# CPU_22032016.net
KiCad netlist of a schematic drawn in Altium Designer
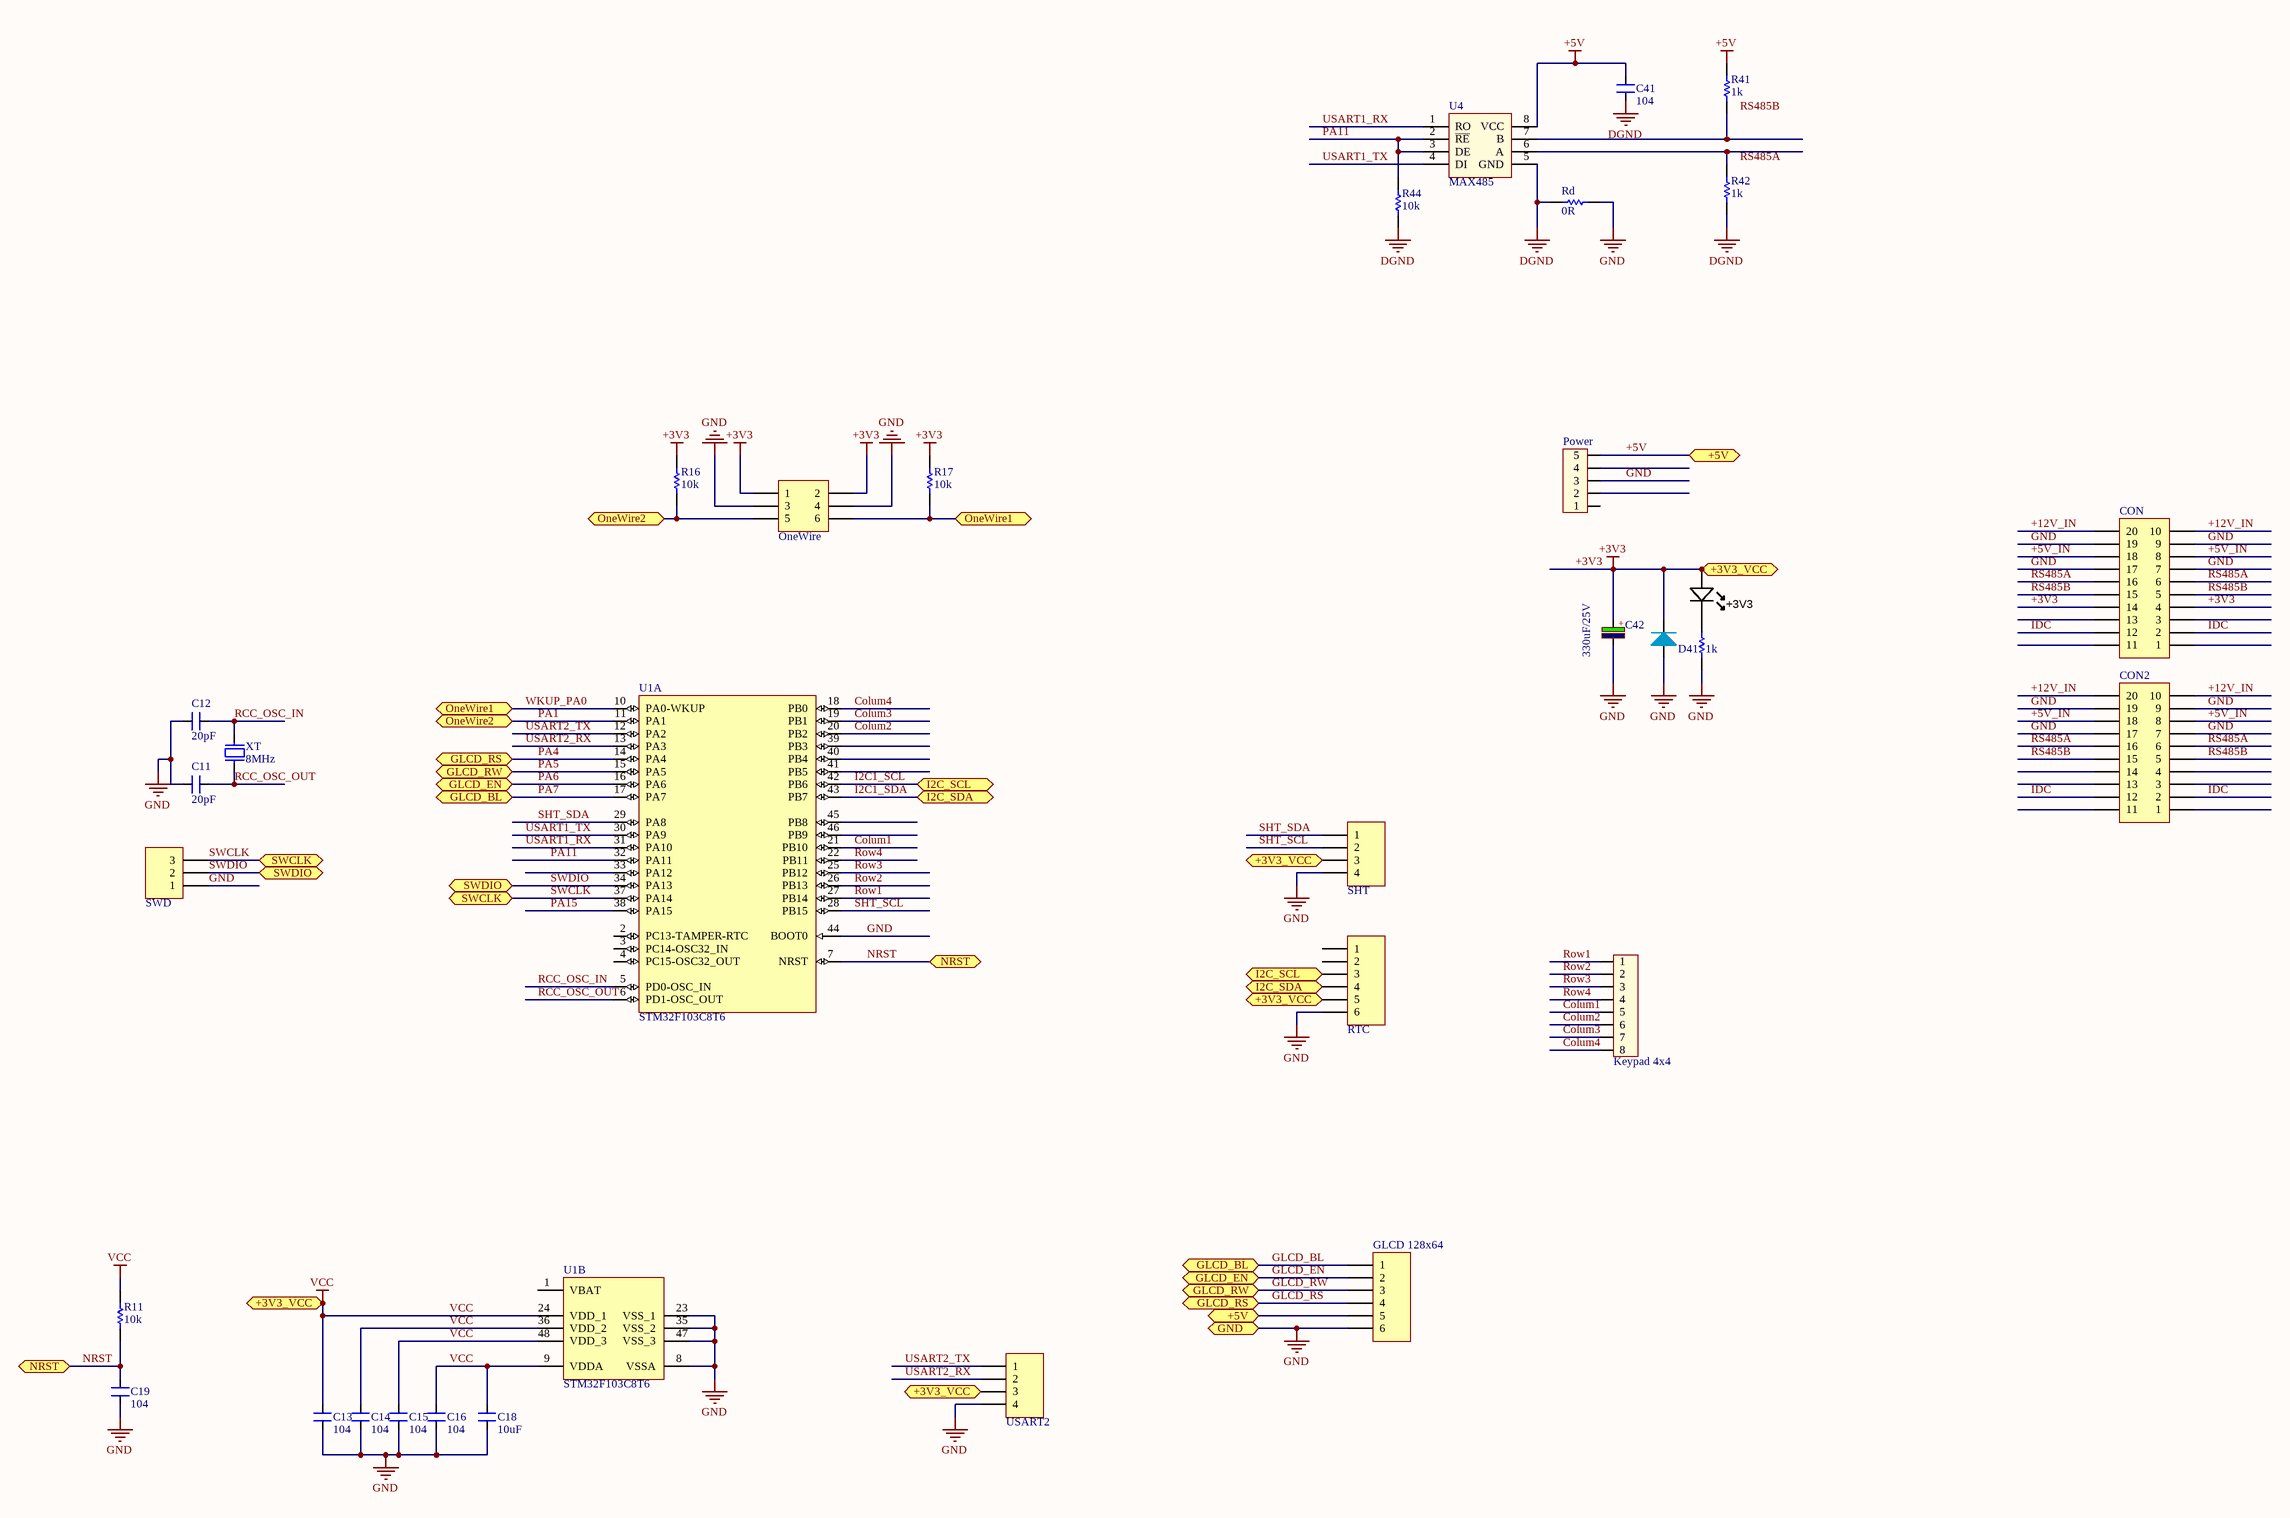
[diagram p0: CPU_22032016.SchDoc]

(export (version "E")
  (design (tool "Eeschema 10.0.6"))
  (components
    (comp (ref "+3V3")
      (value "Blue")
      (footprint "LED-0805-K")
      (description "LED 0805 SMD Blue 100mcd 470nm")
      (libsource (lib "PBL - Light Sources") (part "LED_SMD_Blue_0805_100mcd"))
    )
    (comp (ref "C11")
      (value "20pF")
      (footprint "CAPC1608N")
      (fields (field (name "Comment") "Cap_22p_0603"))
      (libsource (lib "Tuan") (part "CAP NP"))
    )
    (comp (ref "C12")
      (value "20pF")
      (footprint "CAPC1608N")
      (fields (field (name "Comment") "Cap_22p_0603"))
      (libsource (lib "Tuan") (part "CAP NP"))
    )
    (comp (ref "C13")
      (value "104")
      (footprint "CAPC1608N")
      (fields (field (name "Comment") "Cap_104_0603"))
      (libsource (lib "Tuan") (part "CAP NP"))
    )
    (comp (ref "C14")
      (value "104")
      (footprint "CAPC1608N")
      (fields (field (name "Comment") "Cap_104_0603"))
      (libsource (lib "Tuan") (part "CAP NP"))
    )
    (comp (ref "C15")
      (value "104")
      (footprint "CAPC1608N")
      (fields (field (name "Comment") "Cap_104_0603"))
      (libsource (lib "Tuan") (part "CAP NP"))
    )
    (comp (ref "C16")
      (value "104")
      (footprint "CAPC1608N")
      (fields (field (name "Comment") "Cap_104_0603"))
      (libsource (lib "Tuan") (part "CAP NP"))
    )
    (comp (ref "C18")
      (value "10uF")
      (footprint "CAPC2012N_F")
      (fields (field (name "Comment") "Cap_10uF_0805"))
      (libsource (lib "Tuan") (part "CAP NP"))
    )
    (comp (ref "C19")
      (value "104")
      (footprint "CAPC1608N")
      (fields (field (name "Comment") "Cap_104_0603"))
      (libsource (lib "Tuan") (part "CAP NP"))
    )
    (comp (ref "C41")
      (value "104")
      (footprint "CAPC2012N_F")
      (fields (field (name "Comment") "100nF/104"))
      (libsource (lib "Tuan") (part "CAP NP"))
    )
    (comp (ref "C42")
      (value "330uF/25V")
      (footprint "CAPMP3528X210N")
      (description "Cap 1000uF/16V - 220uF/50V")
      (libsource (lib "heromap") (part "CP4"))
    )
    (comp (ref "CON")
      (value "Header 10X2A")
      (footprint "OMC10")
      (description "Header, 10-Pin, Dual row")
      (fields (field (name "PUBLISHER") "Altium Limited"))
      (libsource (lib "Miscellaneous Connectors") (part "Header 10X2A"))
    )
    (comp (ref "CON2")
      (value "Header 10X2A")
      (footprint "OMC10")
      (description "Header, 10-Pin, Dual row")
      (fields (field (name "PUBLISHER") "Altium Limited"))
      (libsource (lib "Miscellaneous Connectors") (part "Header 10X2A"))
    )
    (comp (ref "D41") (value "Diode") (footprint "DO-214AC") (libsource (lib "Tuan") (part "Diode")))
    (comp (ref "GLCD 128x64")
      (value "Header 6")
      (footprint "HDR1X6")
      (description "Header, 6-Pin")
      (fields (field (name "PUBLISHER") "Altium Limited"))
      (libsource (lib "Miscellaneous Connectors") (part "Header 6"))
    )
    (comp (ref "Keypad 4x4")
      (value "JP8")
      (footprint "CON8")
      (description "Connector 8")
      (libsource (lib "syhaunguyen") (part "Con8"))
    )
    (comp (ref "OneWire")
      (value "Header 3X2")
      (footprint "heromap:HDR2X3")
      (description "Header, 3-Pin, Dual row")
      (fields (field (name "PUBLISHER") "Altium Limited"))
      (libsource (lib "heromap") (part "Header 3X2"))
    )
    (comp (ref "Power")
      (value "JP5")
      (footprint "heromap:CON5")
      (description "Connector 5")
      (libsource (lib "heromap") (part "Con5"))
    )
    (comp (ref "R11")
      (value "10k")
      (footprint "RESC1608N_F")
      (fields (field (name "Comment") "Res_10k_0603"))
      (libsource (lib "Tuan") (part "Res"))
    )
    (comp (ref "R16")
      (value "10k")
      (footprint "RESC2012N_F")
      (fields (field (name "Comment") "Res"))
      (libsource (lib "Tuan") (part "Res"))
    )
    (comp (ref "R17")
      (value "10k")
      (footprint "RESC2012N_F")
      (fields (field (name "Comment") "Res"))
      (libsource (lib "Tuan") (part "Res"))
    )
    (comp (ref "R41")
      (value "1k")
      (footprint "RESC2012N_F")
      (description "Tro dan")
      (libsource (lib "GPS_Clock_v12") (part "Res"))
    )
    (comp (ref "R42")
      (value "1k")
      (footprint "RESC2012N_F")
      (description "Tro dan")
      (libsource (lib "GPS_Clock_v12") (part "Res"))
    )
    (comp (ref "R44")
      (value "10k")
      (footprint "RESC2012N_F")
      (description "Tro dan")
      (fields (field (name "Comment") "330R"))
      (libsource (lib "GPS_Clock_v12") (part "Res"))
    )
    (comp (ref "Rd")
      (value "0R")
      (footprint "RESC2012N_F")
      (fields (field (name "Comment") "Res"))
      (libsource (lib "Tuan") (part "Res"))
    )
    (comp (ref "Rled")
      (value "1k")
      (footprint "RESC2012N_F")
      (fields (field (name "Comment") "Res_0805_1k"))
      (libsource (lib "Tuan") (part "Res"))
    )
    (comp (ref "RTC")
      (value "Header 6")
      (footprint "heromap:HDR1X6")
      (description "Header, 6-Pin")
      (fields (field (name "PUBLISHER") "Altium Limited"))
      (libsource (lib "heromap") (part "Header 6"))
    )
    (comp (ref "SHT")
      (value "Header 4")
      (footprint "heromap:HDR1X4")
      (description "Header, 4-Pin")
      (fields (field (name "PUBLISHER") "Altium Limited"))
      (libsource (lib "heromap") (part "Header 4"))
    )
    (comp (ref "SWD")
      (value "Header 3")
      (footprint "heromap:HDR1X3")
      (description "Header, 3-Pin")
      (fields (field (name "PUBLISHER") "Altium Limited"))
      (libsource (lib "heromap") (part "Header 3"))
    )
    (comp (ref "U1")
      (value "STM32F103C8T6")
      (footprint "LQFT48N")
      (libsource (lib "STMicroelectronics STM32 F1") (part "STM32F103C8T6"))
    )
    (comp (ref "U4")
      (value "MAX485")
      (footprint "SO-8")
      (description "RS232 - RS485 (Same sn75176)")
      (libsource (lib "heromap") (part "MAX485"))
    )
    (comp (ref "USART2")
      (value "Header 4")
      (footprint "heromap:HDR1X4")
      (description "Header, 4-Pin")
      (fields (field (name "PUBLISHER") "Altium Limited"))
      (libsource (lib "heromap") (part "Header 4"))
    )
    (comp (ref "XT") (value "8MHz") (footprint "XT2") (libsource (lib "Tuan") (part "Crystal")))
  )
  (nets
    (net (code "1") (name "+3V3") (class "Default")
      (node (ref "+3V3") (pin "A") (pinfunction "A_A") (pintype "passive"))
      (node (ref "C13") (pin "2") (pinfunction "2_2") (pintype "passive"))
      (node (ref "C14") (pin "2") (pinfunction "2_2") (pintype "passive"))
      (node (ref "C15") (pin "2") (pinfunction "2_2") (pintype "passive"))
      (node (ref "C16") (pin "2") (pinfunction "2_2") (pintype "passive"))
      (node (ref "C18") (pin "2") (pinfunction "2_2") (pintype "passive"))
      (node (ref "C42") (pin "1") (pinfunction "1_1") (pintype "passive"))
      (node (ref "CON") (pin "14") (pinfunction "14_14") (pintype "passive"))
      (node (ref "CON") (pin "4") (pinfunction "4_4") (pintype "passive"))
      (node (ref "D41") (pin "2") (pinfunction "K_2") (pintype "passive"))
      (node (ref "OneWire") (pin "1") (pinfunction "1_1") (pintype "passive"))
      (node (ref "OneWire") (pin "2") (pinfunction "2_2") (pintype "passive"))
      (node (ref "R11") (pin "2") (pinfunction "2_2") (pintype "passive"))
      (node (ref "R16") (pin "2") (pinfunction "2_2") (pintype "passive"))
      (node (ref "R17") (pin "2") (pinfunction "2_2") (pintype "passive"))
      (node (ref "RTC") (pin "5") (pinfunction "5_5") (pintype "passive"))
      (node (ref "SHT") (pin "3") (pinfunction "3_3") (pintype "passive"))
      (node (ref "U1") (pin "24") (pinfunction "VDD_1_24") (pintype "power_in"))
      (node (ref "U1") (pin "36") (pinfunction "VDD_2_36") (pintype "power_in"))
      (node (ref "U1") (pin "48") (pinfunction "VDD_3_48") (pintype "power_in"))
      (node (ref "U1") (pin "9") (pinfunction "VDDA_9") (pintype "power_in"))
      (node (ref "USART2") (pin "3") (pinfunction "3_3") (pintype "passive"))
    )
    (net (code "2") (name "+5V") (class "Default")
      (node (ref "C41") (pin "2") (pinfunction "2_2") (pintype "passive"))
      (node (ref "GLCD 128x64") (pin "5") (pinfunction "5_5") (pintype "passive"))
      (node (ref "Power") (pin "5") (pinfunction "5_5") (pintype "passive"))
      (node (ref "R41") (pin "2") (pinfunction "2_2") (pintype "passive"))
      (node (ref "U4") (pin "8") (pinfunction "VCC_8") (pintype "passive"))
    )
    (net (code "3") (name "/+5V_IN") (class "Default")
      (node (ref "CON") (pin "18") (pinfunction "18_18") (pintype "passive"))
      (node (ref "CON") (pin "8") (pinfunction "8_8") (pintype "passive"))
      (node (ref "CON2") (pin "18") (pinfunction "18_18") (pintype "passive"))
      (node (ref "CON2") (pin "8") (pinfunction "8_8") (pintype "passive"))
    )
    (net (code "4") (name "/+12V_IN") (class "Default")
      (node (ref "CON") (pin "10") (pinfunction "10_10") (pintype "passive"))
      (node (ref "CON") (pin "20") (pinfunction "20_20") (pintype "passive"))
      (node (ref "CON2") (pin "10") (pinfunction "10_10") (pintype "passive"))
      (node (ref "CON2") (pin "20") (pinfunction "20_20") (pintype "passive"))
    )
    (net (code "5") (name "/Colum1") (class "Default")
      (node (ref "Keypad 4x4") (pin "5") (pinfunction "5_5") (pintype "passive"))
      (node (ref "U1") (pin "21") (pinfunction "PB10_21") (pintype "bidirectional"))
    )
    (net (code "6") (name "/Colum2") (class "Default")
      (node (ref "Keypad 4x4") (pin "6") (pinfunction "6_6") (pintype "passive"))
      (node (ref "U1") (pin "20") (pinfunction "PB2_20") (pintype "bidirectional"))
    )
    (net (code "7") (name "/Colum3") (class "Default")
      (node (ref "Keypad 4x4") (pin "7") (pinfunction "7_7") (pintype "passive"))
      (node (ref "U1") (pin "19") (pinfunction "PB1_19") (pintype "bidirectional"))
    )
    (net (code "8") (name "/Colum4") (class "Default")
      (node (ref "Keypad 4x4") (pin "8") (pinfunction "8_8") (pintype "passive"))
      (node (ref "U1") (pin "18") (pinfunction "PB0_18") (pintype "bidirectional"))
    )
    (net (code "9") (name "/GLCD_BL") (class "Default")
      (node (ref "GLCD 128x64") (pin "1") (pinfunction "1_1") (pintype "passive"))
      (node (ref "U1") (pin "17") (pinfunction "PA7_17") (pintype "bidirectional"))
    )
    (net (code "10") (name "/GLCD_EN") (class "Default")
      (node (ref "GLCD 128x64") (pin "2") (pinfunction "2_2") (pintype "passive"))
      (node (ref "U1") (pin "16") (pinfunction "PA6_16") (pintype "bidirectional"))
    )
    (net (code "11") (name "/GLCD_RS") (class "Default")
      (node (ref "GLCD 128x64") (pin "4") (pinfunction "4_4") (pintype "passive"))
      (node (ref "U1") (pin "14") (pinfunction "PA4_14") (pintype "bidirectional"))
    )
    (net (code "12") (name "/GLCD_RW") (class "Default")
      (node (ref "GLCD 128x64") (pin "3") (pinfunction "3_3") (pintype "passive"))
      (node (ref "U1") (pin "15") (pinfunction "PA5_15") (pintype "bidirectional"))
    )
    (net (code "13") (name "/I2C1_SCL") (class "Default")
      (node (ref "RTC") (pin "3") (pinfunction "3_3") (pintype "passive"))
      (node (ref "U1") (pin "42") (pinfunction "PB6_42") (pintype "bidirectional"))
    )
    (net (code "14") (name "/I2C1_SDA") (class "Default")
      (node (ref "RTC") (pin "4") (pinfunction "4_4") (pintype "passive"))
      (node (ref "U1") (pin "43") (pinfunction "PB7_43") (pintype "bidirectional"))
    )
    (net (code "15") (name "/IDC") (class "Default")
      (node (ref "CON") (pin "12") (pinfunction "12_12") (pintype "passive"))
      (node (ref "CON") (pin "2") (pinfunction "2_2") (pintype "passive"))
      (node (ref "CON2") (pin "12") (pinfunction "12_12") (pintype "passive"))
      (node (ref "CON2") (pin "2") (pinfunction "2_2") (pintype "passive"))
    )
    (net (code "16") (name "/NRST") (class "Default")
      (node (ref "C19") (pin "2") (pinfunction "2_2") (pintype "passive"))
      (node (ref "R11") (pin "1") (pinfunction "1_1") (pintype "passive"))
      (node (ref "U1") (pin "7") (pinfunction "NRST_7") (pintype "bidirectional"))
    )
    (net (code "17") (name "/PA1") (class "Default")
      (node (ref "OneWire") (pin "5") (pinfunction "5_5") (pintype "passive"))
      (node (ref "R16") (pin "1") (pinfunction "1_1") (pintype "passive"))
      (node (ref "U1") (pin "11") (pinfunction "PA1_11") (pintype "bidirectional"))
    )
    (net (code "18") (name "/PA11") (class "Default")
      (node (ref "R44") (pin "2") (pinfunction "2_2") (pintype "passive"))
      (node (ref "U1") (pin "32") (pinfunction "PA11_32") (pintype "bidirectional"))
      (node (ref "U4") (pin "2") (pinfunction "~{RE}_2") (pintype "passive"))
      (node (ref "U4") (pin "3") (pinfunction "DE_3") (pintype "passive"))
    )
    (net (code "19") (name "/PA15") (class "Default")
      (node (ref "U1") (pin "38") (pinfunction "PA15_38") (pintype "bidirectional"))
    )
    (net (code "20") (name "/RCC_OSC_IN") (class "Default")
      (node (ref "C12") (pin "1") (pinfunction "1_1") (pintype "passive"))
      (node (ref "U1") (pin "5") (pinfunction "PD0-OSC_IN_5") (pintype "bidirectional"))
      (node (ref "XT") (pin "2") (pinfunction "2_2") (pintype "passive"))
    )
    (net (code "21") (name "/RCC_OSC_OUT") (class "Default")
      (node (ref "C11") (pin "1") (pinfunction "1_1") (pintype "passive"))
      (node (ref "U1") (pin "6") (pinfunction "PD1-OSC_OUT_6") (pintype "bidirectional"))
      (node (ref "XT") (pin "1") (pinfunction "1_1") (pintype "passive"))
    )
    (net (code "22") (name "/RS485A") (class "Default")
      (node (ref "CON") (pin "16") (pinfunction "16_16") (pintype "passive"))
      (node (ref "CON") (pin "6") (pinfunction "6_6") (pintype "passive"))
      (node (ref "CON2") (pin "16") (pinfunction "16_16") (pintype "passive"))
      (node (ref "CON2") (pin "6") (pinfunction "6_6") (pintype "passive"))
    )
    (net (code "23") (name "/RS485B") (class "Default")
      (node (ref "CON") (pin "15") (pinfunction "15_15") (pintype "passive"))
      (node (ref "CON") (pin "5") (pinfunction "5_5") (pintype "passive"))
      (node (ref "CON2") (pin "15") (pinfunction "15_15") (pintype "passive"))
      (node (ref "CON2") (pin "5") (pinfunction "5_5") (pintype "passive"))
    )
    (net (code "24") (name "/Row1") (class "Default")
      (node (ref "Keypad 4x4") (pin "1") (pinfunction "1_1") (pintype "passive"))
      (node (ref "U1") (pin "27") (pinfunction "PB14_27") (pintype "bidirectional"))
    )
    (net (code "25") (name "/Row2") (class "Default")
      (node (ref "Keypad 4x4") (pin "2") (pinfunction "2_2") (pintype "passive"))
      (node (ref "U1") (pin "26") (pinfunction "PB13_26") (pintype "bidirectional"))
    )
    (net (code "26") (name "/Row3") (class "Default")
      (node (ref "Keypad 4x4") (pin "3") (pinfunction "3_3") (pintype "passive"))
      (node (ref "U1") (pin "25") (pinfunction "PB12_25") (pintype "bidirectional"))
    )
    (net (code "27") (name "/Row4") (class "Default")
      (node (ref "Keypad 4x4") (pin "4") (pinfunction "4_4") (pintype "passive"))
      (node (ref "U1") (pin "22") (pinfunction "PB11_22") (pintype "bidirectional"))
    )
    (net (code "28") (name "/SHT_SCL") (class "Default")
      (node (ref "SHT") (pin "2") (pinfunction "2_2") (pintype "passive"))
      (node (ref "U1") (pin "28") (pinfunction "PB15_28") (pintype "bidirectional"))
    )
    (net (code "29") (name "/SHT_SDA") (class "Default")
      (node (ref "SHT") (pin "1") (pinfunction "1_1") (pintype "passive"))
      (node (ref "U1") (pin "29") (pinfunction "PA8_29") (pintype "bidirectional"))
    )
    (net (code "30") (name "/SWCLK") (class "Default")
      (node (ref "SWD") (pin "3") (pinfunction "3_3") (pintype "passive"))
      (node (ref "U1") (pin "37") (pinfunction "PA14_37") (pintype "bidirectional"))
    )
    (net (code "31") (name "/SWDIO") (class "Default")
      (node (ref "SWD") (pin "2") (pinfunction "2_2") (pintype "passive"))
      (node (ref "U1") (pin "34") (pinfunction "PA13_34") (pintype "bidirectional"))
    )
    (net (code "32") (name "/USART1_RX") (class "Default")
      (node (ref "U1") (pin "31") (pinfunction "PA10_31") (pintype "bidirectional"))
      (node (ref "U4") (pin "1") (pinfunction "RO_1") (pintype "passive"))
    )
    (net (code "33") (name "/USART1_TX") (class "Default")
      (node (ref "U1") (pin "30") (pinfunction "PA9_30") (pintype "bidirectional"))
      (node (ref "U4") (pin "4") (pinfunction "DI_4") (pintype "passive"))
    )
    (net (code "34") (name "/USART2_RX") (class "Default")
      (node (ref "U1") (pin "13") (pinfunction "PA3_13") (pintype "bidirectional"))
      (node (ref "USART2") (pin "2") (pinfunction "2_2") (pintype "passive"))
    )
    (net (code "35") (name "/USART2_TX") (class "Default")
      (node (ref "U1") (pin "12") (pinfunction "PA2_12") (pintype "bidirectional"))
      (node (ref "USART2") (pin "1") (pinfunction "1_1") (pintype "passive"))
    )
    (net (code "36") (name "/WKUP_PA0") (class "Default")
      (node (ref "OneWire") (pin "6") (pinfunction "6_6") (pintype "passive"))
      (node (ref "R17") (pin "1") (pinfunction "1_1") (pintype "passive"))
      (node (ref "U1") (pin "10") (pinfunction "PA0-WKUP_10") (pintype "bidirectional"))
    )
    (net (code "37") (name "DGND") (class "Default")
      (node (ref "C41") (pin "1") (pinfunction "1_1") (pintype "passive"))
      (node (ref "R42") (pin "1") (pinfunction "1_1") (pintype "passive"))
      (node (ref "R44") (pin "1") (pinfunction "1_1") (pintype "passive"))
      (node (ref "Rd") (pin "1") (pinfunction "1_1") (pintype "passive"))
      (node (ref "U4") (pin "5") (pinfunction "GND_5") (pintype "passive"))
    )
    (net (code "38") (name "GND") (class "Default")
      (node (ref "C11") (pin "2") (pinfunction "2_2") (pintype "passive"))
      (node (ref "C12") (pin "2") (pinfunction "2_2") (pintype "passive"))
      (node (ref "C13") (pin "1") (pinfunction "1_1") (pintype "passive"))
      (node (ref "C14") (pin "1") (pinfunction "1_1") (pintype "passive"))
      (node (ref "C15") (pin "1") (pinfunction "1_1") (pintype "passive"))
      (node (ref "C16") (pin "1") (pinfunction "1_1") (pintype "passive"))
      (node (ref "C18") (pin "1") (pinfunction "1_1") (pintype "passive"))
      (node (ref "C19") (pin "1") (pinfunction "1_1") (pintype "passive"))
      (node (ref "C42") (pin "2") (pinfunction "2_2") (pintype "passive"))
      (node (ref "CON") (pin "17") (pinfunction "17_17") (pintype "passive"))
      (node (ref "CON") (pin "19") (pinfunction "19_19") (pintype "passive"))
      (node (ref "CON") (pin "7") (pinfunction "7_7") (pintype "passive"))
      (node (ref "CON") (pin "9") (pinfunction "9_9") (pintype "passive"))
      (node (ref "CON2") (pin "17") (pinfunction "17_17") (pintype "passive"))
      (node (ref "CON2") (pin "19") (pinfunction "19_19") (pintype "passive"))
      (node (ref "CON2") (pin "7") (pinfunction "7_7") (pintype "passive"))
      (node (ref "CON2") (pin "9") (pinfunction "9_9") (pintype "passive"))
      (node (ref "D41") (pin "1") (pinfunction "A_1") (pintype "passive"))
      (node (ref "GLCD 128x64") (pin "6") (pinfunction "6_6") (pintype "passive"))
      (node (ref "OneWire") (pin "3") (pinfunction "3_3") (pintype "passive"))
      (node (ref "OneWire") (pin "4") (pinfunction "4_4") (pintype "passive"))
      (node (ref "Power") (pin "3") (pinfunction "3_3") (pintype "passive"))
      (node (ref "RTC") (pin "6") (pinfunction "6_6") (pintype "passive"))
      (node (ref "Rd") (pin "2") (pinfunction "2_2") (pintype "passive"))
      (node (ref "Rled") (pin "2") (pinfunction "2_2") (pintype "passive"))
      (node (ref "SHT") (pin "4") (pinfunction "4_4") (pintype "passive"))
      (node (ref "SWD") (pin "1") (pinfunction "1_1") (pintype "passive"))
      (node (ref "U1") (pin "23") (pinfunction "VSS_1_23") (pintype "power_in"))
      (node (ref "U1") (pin "35") (pinfunction "VSS_2_35") (pintype "power_in"))
      (node (ref "U1") (pin "44") (pinfunction "BOOT0_44") (pintype "input"))
      (node (ref "U1") (pin "47") (pinfunction "VSS_3_47") (pintype "power_in"))
      (node (ref "U1") (pin "8") (pinfunction "VSSA_8") (pintype "power_in"))
      (node (ref "USART2") (pin "4") (pinfunction "4_4") (pintype "passive"))
    )
    (net (code "39") (name "Net-(+3V3-PadK)") (class "Default")
      (node (ref "+3V3") (pin "K") (pinfunction "K_K") (pintype "passive"))
      (node (ref "Rled") (pin "1") (pinfunction "1_1") (pintype "passive"))
    )
    (net (code "40") (name "Net-(U4-A)") (class "Default")
      (node (ref "R42") (pin "2") (pinfunction "2_2") (pintype "passive"))
      (node (ref "U4") (pin "6") (pinfunction "A_6") (pintype "passive"))
    )
    (net (code "41") (name "Net-(U4-B)") (class "Default")
      (node (ref "R41") (pin "1") (pinfunction "1_1") (pintype "passive"))
      (node (ref "U4") (pin "7") (pinfunction "B_7") (pintype "passive"))
    )
    (net (code "42") (name "unconnected-(CON-Pad1)") (class "Default")
      (node (ref "CON") (pin "1") (pinfunction "1_1") (pintype "passive"))
    )
    (net (code "43") (name "unconnected-(CON-Pad3)") (class "Default")
      (node (ref "CON") (pin "3") (pinfunction "3_3") (pintype "passive"))
    )
    (net (code "44") (name "unconnected-(CON-Pad11)") (class "Default")
      (node (ref "CON") (pin "11") (pinfunction "11_11") (pintype "passive"))
    )
    (net (code "45") (name "unconnected-(CON-Pad13)") (class "Default")
      (node (ref "CON") (pin "13") (pinfunction "13_13") (pintype "passive"))
    )
    (net (code "46") (name "unconnected-(CON2-Pad1)") (class "Default")
      (node (ref "CON2") (pin "1") (pinfunction "1_1") (pintype "passive"))
    )
    (net (code "47") (name "unconnected-(CON2-Pad3)") (class "Default")
      (node (ref "CON2") (pin "3") (pinfunction "3_3") (pintype "passive"))
    )
    (net (code "48") (name "unconnected-(CON2-Pad4)") (class "Default")
      (node (ref "CON2") (pin "4") (pinfunction "4_4") (pintype "passive"))
    )
    (net (code "49") (name "unconnected-(CON2-Pad11)") (class "Default")
      (node (ref "CON2") (pin "11") (pinfunction "11_11") (pintype "passive"))
    )
    (net (code "50") (name "unconnected-(CON2-Pad13)") (class "Default")
      (node (ref "CON2") (pin "13") (pinfunction "13_13") (pintype "passive"))
    )
    (net (code "51") (name "unconnected-(CON2-Pad14)") (class "Default")
      (node (ref "CON2") (pin "14") (pinfunction "14_14") (pintype "passive"))
    )
    (net (code "52") (name "unconnected-(Power-Pad1)") (class "Default")
      (node (ref "Power") (pin "1") (pinfunction "1_1") (pintype "passive"))
    )
    (net (code "53") (name "unconnected-(Power-Pad2)") (class "Default")
      (node (ref "Power") (pin "2") (pinfunction "2_2") (pintype "passive"))
    )
    (net (code "54") (name "unconnected-(Power-Pad4)") (class "Default")
      (node (ref "Power") (pin "4") (pinfunction "4_4") (pintype "passive"))
    )
    (net (code "55") (name "unconnected-(RTC-Pad1)") (class "Default")
      (node (ref "RTC") (pin "1") (pinfunction "1_1") (pintype "passive"))
    )
    (net (code "56") (name "unconnected-(RTC-Pad2)") (class "Default")
      (node (ref "RTC") (pin "2") (pinfunction "2_2") (pintype "passive"))
    )
    (net (code "57") (name "unconnected-(U1A-PA12-Pad33)") (class "Default")
      (node (ref "U1") (pin "33") (pinfunction "PA12_33") (pintype "bidirectional"))
    )
    (net (code "58") (name "unconnected-(U1A-PB3-Pad39)") (class "Default")
      (node (ref "U1") (pin "39") (pinfunction "PB3_39") (pintype "bidirectional"))
    )
    (net (code "59") (name "unconnected-(U1A-PB4-Pad40)") (class "Default")
      (node (ref "U1") (pin "40") (pinfunction "PB4_40") (pintype "bidirectional"))
    )
    (net (code "60") (name "unconnected-(U1A-PB5-Pad41)") (class "Default")
      (node (ref "U1") (pin "41") (pinfunction "PB5_41") (pintype "bidirectional"))
    )
    (net (code "61") (name "unconnected-(U1A-PB8-Pad45)") (class "Default")
      (node (ref "U1") (pin "45") (pinfunction "PB8_45") (pintype "bidirectional"))
    )
    (net (code "62") (name "unconnected-(U1A-PB9-Pad46)") (class "Default")
      (node (ref "U1") (pin "46") (pinfunction "PB9_46") (pintype "bidirectional"))
    )
    (net (code "63") (name "unconnected-(U1A-PC13-TAMPER-RTC-Pad2)") (class "Default")
      (node (ref "U1") (pin "2") (pinfunction "PC13-TAMPER-RTC_2") (pintype "bidirectional"))
    )
    (net (code "64") (name "unconnected-(U1A-PC14-OSC32_IN-Pad3)") (class "Default")
      (node (ref "U1") (pin "3") (pinfunction "PC14-OSC32_IN_3") (pintype "bidirectional"))
    )
    (net (code "65") (name "unconnected-(U1A-PC15-OSC32_OUT-Pad4)") (class "Default")
      (node (ref "U1") (pin "4") (pinfunction "PC15-OSC32_OUT_4") (pintype "bidirectional"))
    )
    (net (code "66") (name "unconnected-(U1B-VBAT-Pad1)") (class "Default")
      (node (ref "U1") (pin "1") (pinfunction "VBAT_1") (pintype "power_in"))
    )
  )
)
